# Baby_oscar_doo_do_doo_doo_baby.net
KiCad netlist of a schematic drawn in EAGLE
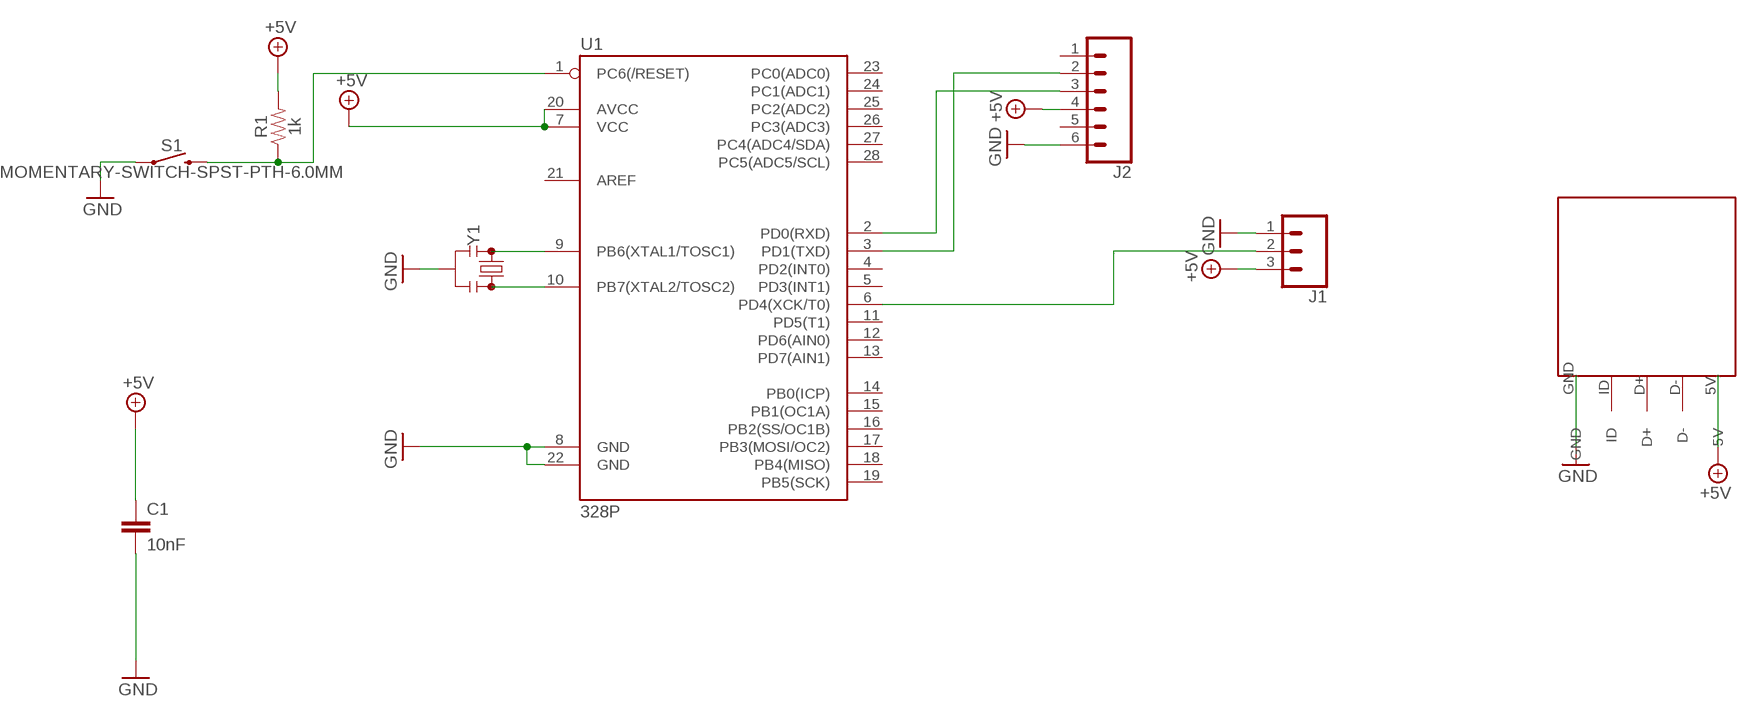
[diagram p0: schematic, sheet 1]

(export (version "E")
  (design (tool "Eeschema 10.0.6"))
  (components
    (comp (ref "C1")
      (value "10nF")
      (footprint "eagle-import:CAP-PTH-10MM")
      (libsource (lib "eagle-import") (part "10NF-PTH-10MM-10000V-1-%"))
    )
    (comp (ref "J1")
      (value "CONN_03")
      (footprint "eagle-import:1X03")
      (libsource (lib "eagle-import") (part "CONN_03"))
    )
    (comp (ref "J2")
      (value "CONN_06SILK_FEMALE_PTH")
      (footprint "eagle-import:1X06")
      (libsource (lib "eagle-import") (part "CONN_06SILK_FEMALE_PTH"))
    )
    (comp (ref "R1")
      (value "1k")
      (footprint "eagle-import:AXIAL-0.3")
      (libsource (lib "eagle-import") (part "1KOHM-HORIZ-1/4W-5%"))
    )
    (comp (ref "S1")
      (value "MOMENTARY-SWITCH-SPST-PTH-6.0MM")
      (footprint "eagle-import:TACTILE_SWITCH_PTH_6.0MM")
      (libsource (lib "eagle-import") (part "MOMENTARY-SWITCH-SPST-PTH-6.0MM"))
    )
    (comp (ref "U$1")
      (value "USBCONNECTOR")
      (footprint "eagle-import:USBCONNECTOR")
      (libsource (lib "eagle-import") (part "USBCONNECTOR"))
    )
    (comp (ref "U1")
      (value "328P")
      (footprint "eagle-import:DIP28")
      (libsource (lib "eagle-import") (part "ATMEGA328P_PDIP"))
    )
    (comp (ref "Y1")
      (value "RESONATORPTH-7.6X3.8")
      (footprint "eagle-import:RESONATOR-PTH-7.6X3.8")
      (libsource (lib "eagle-import") (part "RESONATORPTH-7.6X3.8"))
    )
  )
  (nets
    (net (code "1") (name "+5V") (class "Default")
      (node (ref "C1") (pin "1") (pinfunction "1_1") (pintype "passive"))
      (node (ref "J1") (pin "3") (pinfunction "3_3") (pintype "passive"))
      (node (ref "J2") (pin "4") (pinfunction "4_4") (pintype "passive"))
      (node (ref "R1") (pin "P$2") (pinfunction "2_P$2") (pintype "passive"))
      (node (ref "U$1") (pin "5V") (pinfunction "5V_5V") (pintype "bidirectional"))
      (node (ref "U1") (pin "20") (pinfunction "AVCC_20") (pintype "bidirectional"))
      (node (ref "U1") (pin "7") (pinfunction "VCC_7") (pintype "bidirectional"))
    )
    (net (code "2") (name "GND") (class "Default")
      (node (ref "C1") (pin "2") (pinfunction "2_2") (pintype "passive"))
      (node (ref "J1") (pin "1") (pinfunction "1_1") (pintype "passive"))
      (node (ref "J2") (pin "6") (pinfunction "6_6") (pintype "passive"))
      (node (ref "S1") (pin "1") (pinfunction "1_1") (pintype "passive"))
      (node (ref "U$1") (pin "GND") (pinfunction "GND_GND") (pintype "bidirectional"))
      (node (ref "U1") (pin "22") (pinfunction "GND_22") (pintype "bidirectional"))
      (node (ref "U1") (pin "8") (pinfunction "GND_8") (pintype "bidirectional"))
      (node (ref "Y1") (pin "2") (pinfunction "2_2") (pintype "passive"))
    )
    (net (code "3") (name "Net-(R1-1)") (class "Default")
      (node (ref "R1") (pin "P$1") (pinfunction "1_P$1") (pintype "passive"))
      (node (ref "S1") (pin "3") (pinfunction "2_3") (pintype "passive"))
      (node (ref "U1") (pin "1") (pinfunction "PC6(/RESET)_1") (pintype "bidirectional"))
    )
    (net (code "4") (name "Net-(U1-PB6(XTAL1{slash}TOSC1))") (class "Default")
      (node (ref "U1") (pin "9") (pinfunction "PB6(XTAL1/TOSC1)_9") (pintype "bidirectional"))
      (node (ref "Y1") (pin "16MHZ") (pinfunction "1_16MHZ") (pintype "passive"))
    )
    (net (code "5") (name "Net-(U1-PB7(XTAL2{slash}TOSC2))") (class "Default")
      (node (ref "U1") (pin "10") (pinfunction "PB7(XTAL2/TOSC2)_10") (pintype "bidirectional"))
      (node (ref "Y1") (pin "3") (pinfunction "3_3") (pintype "passive"))
    )
    (net (code "6") (name "Net-(U1-PD0(RXD))") (class "Default")
      (node (ref "J2") (pin "3") (pinfunction "3_3") (pintype "passive"))
      (node (ref "U1") (pin "2") (pinfunction "PD0(RXD)_2") (pintype "bidirectional"))
    )
    (net (code "7") (name "Net-(U1-PD1(TXD))") (class "Default")
      (node (ref "J2") (pin "2") (pinfunction "2_2") (pintype "passive"))
      (node (ref "U1") (pin "3") (pinfunction "PD1(TXD)_3") (pintype "bidirectional"))
    )
    (net (code "8") (name "Net-(U1-PD4(XCK{slash}T0))") (class "Default")
      (node (ref "J1") (pin "2") (pinfunction "2_2") (pintype "passive"))
      (node (ref "U1") (pin "6") (pinfunction "PD4(XCK/T0)_6") (pintype "bidirectional"))
    )
    (net (code "9") (name "unconnected-(J2-Pad1)") (class "Default")
      (node (ref "J2") (pin "1") (pinfunction "1_1") (pintype "passive"))
    )
    (net (code "10") (name "unconnected-(J2-Pad5)") (class "Default")
      (node (ref "J2") (pin "5") (pinfunction "5_5") (pintype "passive"))
    )
    (net (code "11") (name "unconnected-(U$1-PadD+)") (class "Default")
      (node (ref "U$1") (pin "D+") (pinfunction "D+_D+") (pintype "bidirectional"))
    )
    (net (code "12") (name "unconnected-(U$1-PadD-)") (class "Default")
      (node (ref "U$1") (pin "D-") (pinfunction "D-_D-") (pintype "bidirectional"))
    )
    (net (code "13") (name "unconnected-(U$1-PadID)") (class "Default")
      (node (ref "U$1") (pin "ID") (pinfunction "ID_ID") (pintype "bidirectional"))
    )
    (net (code "14") (name "unconnected-(U1-AREF-Pad21)") (class "Default")
      (node (ref "U1") (pin "21") (pinfunction "AREF_21") (pintype "bidirectional"))
    )
    (net (code "15") (name "unconnected-(U1-PB0(ICP)-Pad14)") (class "Default")
      (node (ref "U1") (pin "14") (pinfunction "PB0(ICP)_14") (pintype "bidirectional"))
    )
    (net (code "16") (name "unconnected-(U1-PB1(OC1A)-Pad15)") (class "Default")
      (node (ref "U1") (pin "15") (pinfunction "PB1(OC1A)_15") (pintype "bidirectional"))
    )
    (net (code "17") (name "unconnected-(U1-PB2(SS{slash}OC1B)-Pad16)") (class "Default")
      (node (ref "U1") (pin "16") (pinfunction "PB2(SS/OC1B)_16") (pintype "bidirectional"))
    )
    (net (code "18") (name "unconnected-(U1-PB3(MOSI{slash}OC2)-Pad17)") (class "Default")
      (node (ref "U1") (pin "17") (pinfunction "PB3(MOSI/OC2)_17") (pintype "bidirectional"))
    )
    (net (code "19") (name "unconnected-(U1-PB4(MISO)-Pad18)") (class "Default")
      (node (ref "U1") (pin "18") (pinfunction "PB4(MISO)_18") (pintype "bidirectional"))
    )
    (net (code "20") (name "unconnected-(U1-PB5(SCK)-Pad19)") (class "Default")
      (node (ref "U1") (pin "19") (pinfunction "PB5(SCK)_19") (pintype "bidirectional"))
    )
    (net (code "21") (name "unconnected-(U1-PC0(ADC0)-Pad23)") (class "Default")
      (node (ref "U1") (pin "23") (pinfunction "PC0(ADC0)_23") (pintype "bidirectional"))
    )
    (net (code "22") (name "unconnected-(U1-PC1(ADC1)-Pad24)") (class "Default")
      (node (ref "U1") (pin "24") (pinfunction "PC1(ADC1)_24") (pintype "bidirectional"))
    )
    (net (code "23") (name "unconnected-(U1-PC2(ADC2)-Pad25)") (class "Default")
      (node (ref "U1") (pin "25") (pinfunction "PC2(ADC2)_25") (pintype "bidirectional"))
    )
    (net (code "24") (name "unconnected-(U1-PC3(ADC3)-Pad26)") (class "Default")
      (node (ref "U1") (pin "26") (pinfunction "PC3(ADC3)_26") (pintype "bidirectional"))
    )
    (net (code "25") (name "unconnected-(U1-PC4(ADC4{slash}SDA)-Pad27)") (class "Default")
      (node (ref "U1") (pin "27") (pinfunction "PC4(ADC4/SDA)_27") (pintype "bidirectional"))
    )
    (net (code "26") (name "unconnected-(U1-PC5(ADC5{slash}SCL)-Pad28)") (class "Default")
      (node (ref "U1") (pin "28") (pinfunction "PC5(ADC5/SCL)_28") (pintype "bidirectional"))
    )
    (net (code "27") (name "unconnected-(U1-PD2(INT0)-Pad4)") (class "Default")
      (node (ref "U1") (pin "4") (pinfunction "PD2(INT0)_4") (pintype "bidirectional"))
    )
    (net (code "28") (name "unconnected-(U1-PD3(INT1)-Pad5)") (class "Default")
      (node (ref "U1") (pin "5") (pinfunction "PD3(INT1)_5") (pintype "bidirectional"))
    )
    (net (code "29") (name "unconnected-(U1-PD5(T1)-Pad11)") (class "Default")
      (node (ref "U1") (pin "11") (pinfunction "PD5(T1)_11") (pintype "bidirectional"))
    )
    (net (code "30") (name "unconnected-(U1-PD6(AIN0)-Pad12)") (class "Default")
      (node (ref "U1") (pin "12") (pinfunction "PD6(AIN0)_12") (pintype "bidirectional"))
    )
    (net (code "31") (name "unconnected-(U1-PD7(AIN1)-Pad13)") (class "Default")
      (node (ref "U1") (pin "13") (pinfunction "PD7(AIN1)_13") (pintype "bidirectional"))
    )
  )
)
